# Addon-mapleCUx_Raspi-3V3-UART-CC2530-V00.net
KiCad netlist of a schematic drawn in EAGLE
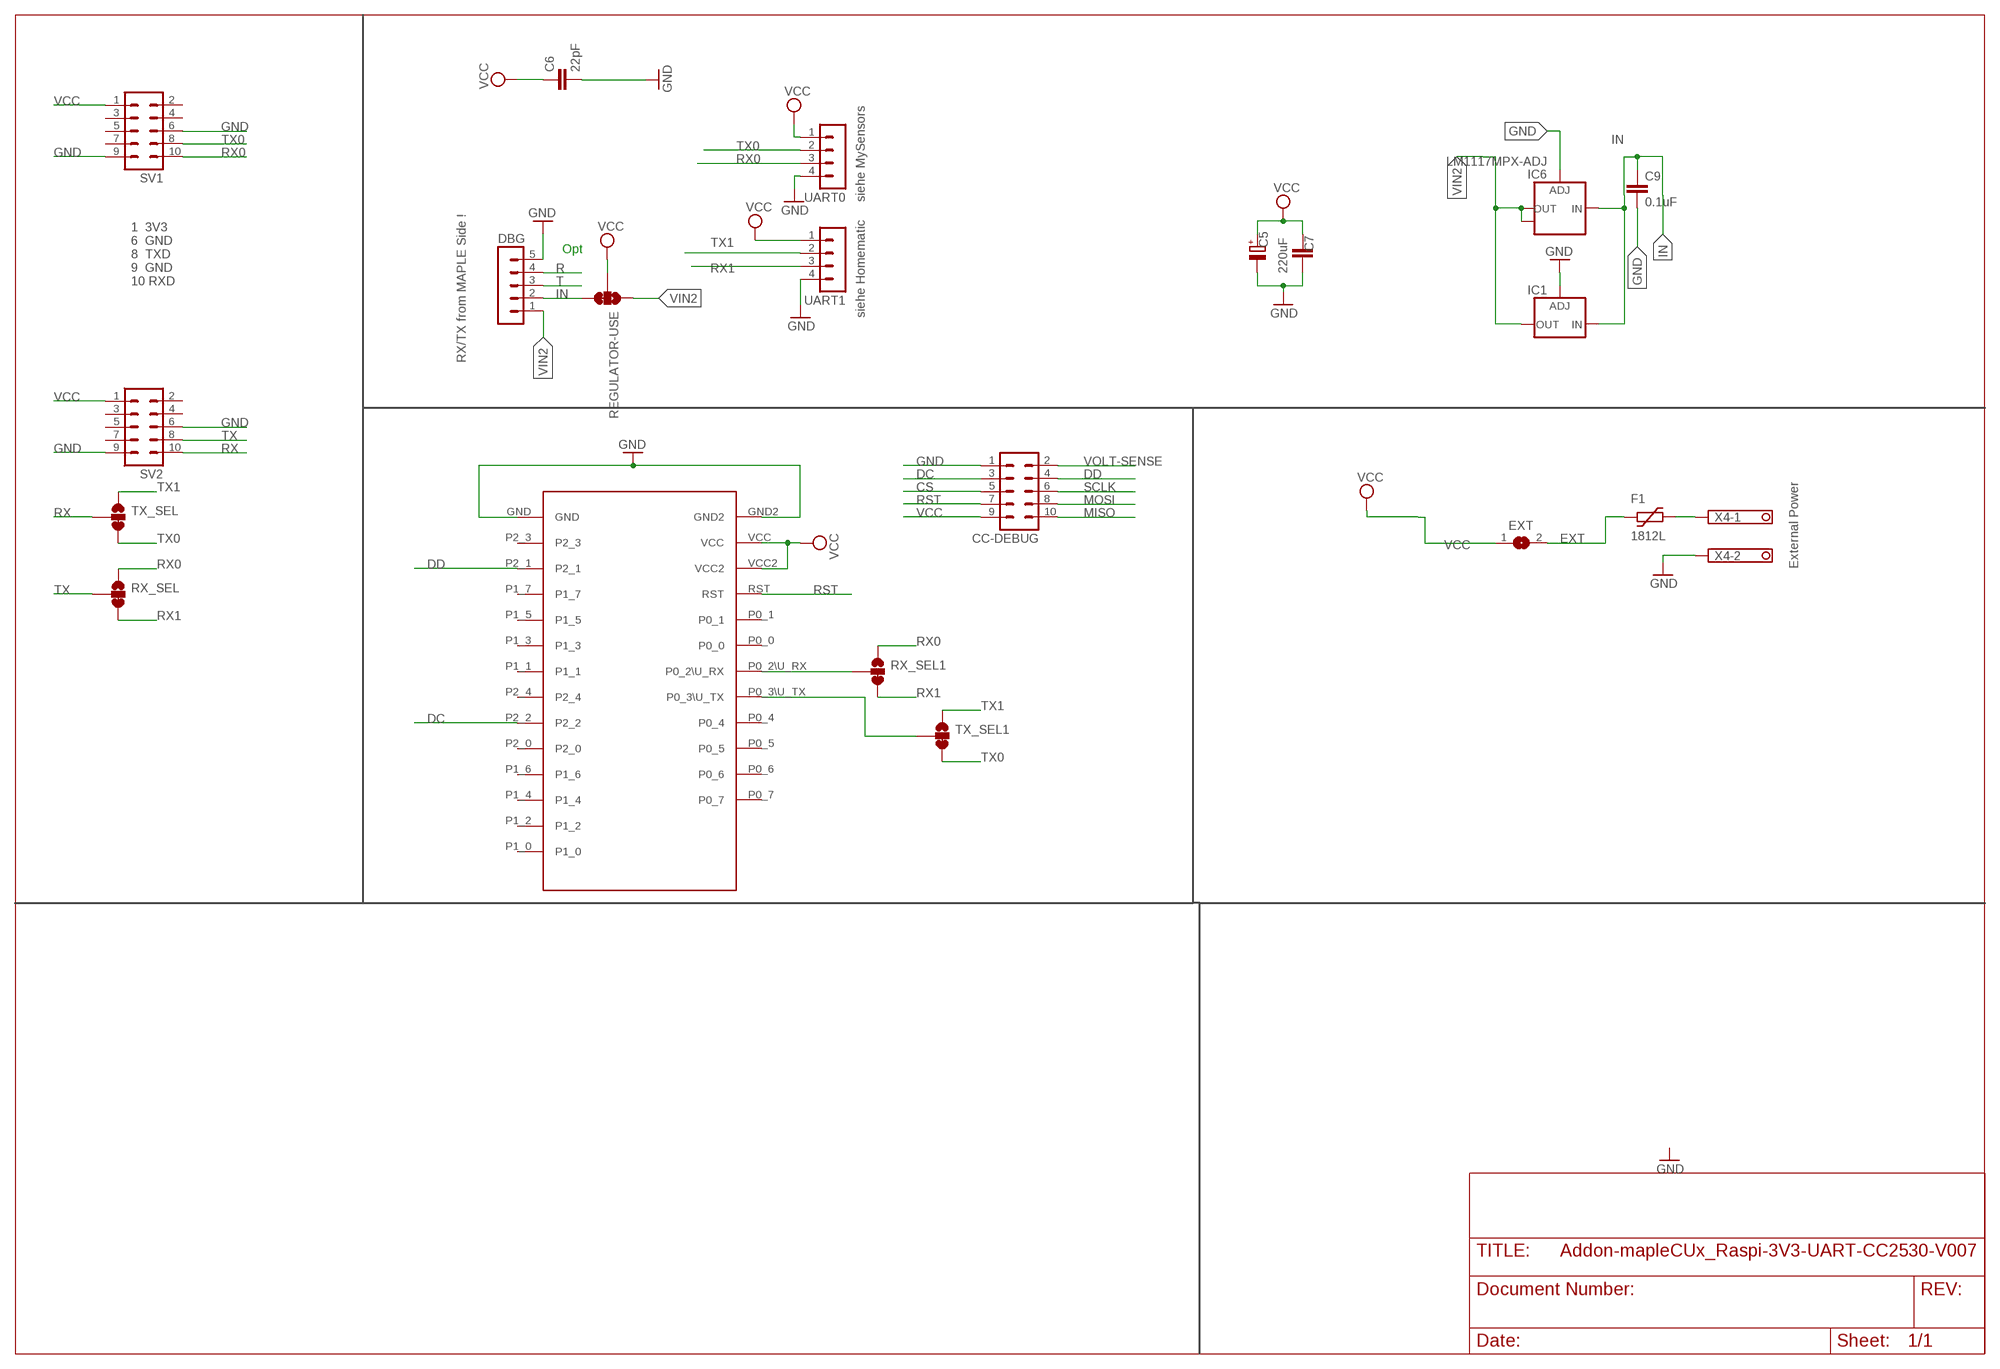
[diagram p0: schematic, sheet 1]

(export (version "E")
  (design (tool "Eeschema 10.0.6"))
  (components
    (comp (ref "C5")
      (value "220uF")
      (footprint "eagle-import:E5-8,5")
      (libsource (lib "eagle-import") (part "CPOL-EUE5-8.5"))
    )
    (comp (ref "C6")
      (value "22pF")
      (footprint "eagle-import:C0805")
      (libsource (lib "eagle-import") (part "C-EUC0805"))
    )
    (comp (ref "C7")
      (value "C-EUC1812")
      (footprint "eagle-import:C1812")
      (libsource (lib "eagle-import") (part "C-EUC1812"))
    )
    (comp (ref "C9")
      (value "0.1uF")
      (footprint "eagle-import:C1206")
      (libsource (lib "eagle-import") (part "C-EUC1206"))
    )
    (comp (ref "CC-DEBUG")
      (value "MA05-2")
      (footprint "eagle-import:MA05-2")
      (libsource (lib "eagle-import") (part "MA05-2"))
    )
    (comp (ref "DBG")
      (value "MA05-1")
      (footprint "eagle-import:MA05-1")
      (libsource (lib "eagle-import") (part "MA05-1"))
    )
    (comp (ref "EXT") (value "SJ") (footprint "eagle-import:SJ") (libsource (lib "eagle-import") (part "SJ")))
    (comp (ref "F1")
      (value "1812L")
      (footprint "eagle-import:1812L")
      (libsource (lib "eagle-import") (part "1812L"))
    )
    (comp (ref "IC1")
      (value "LD117ADT50TR")
      (footprint "eagle-import:DPACK")
      (libsource (lib "eagle-import") (part "LD117A?DT50TR"))
    )
    (comp (ref "IC6")
      (value "LM1117MPX-ADJ")
      (footprint "eagle-import:SOT223")
      (libsource (lib "eagle-import") (part "LM1117MPX-ADJ"))
    )
    (comp (ref "REGULATOR-USE")
      (value "JUMPER-SMT_3_1-NC_TRACE_SILK")
      (footprint "eagle-import:SMT-JUMPER_3_1-NC_TRACE_SILK")
      (libsource (lib "eagle-import") (part "JUMPER-SMT_3_1-NC_TRACE_SILK"))
    )
    (comp (ref "RX_SEL")
      (value "JUMPER-SMT_3_1-NC_TRACE_SILK")
      (footprint "eagle-import:SMT-JUMPER_3_1-NC_TRACE_SILK")
      (libsource (lib "eagle-import") (part "JUMPER-SMT_3_1-NC_TRACE_SILK"))
    )
    (comp (ref "RX_SEL1")
      (value "JUMPER-SMT_3_1-NC_TRACE_SILK")
      (footprint "eagle-import:SMT-JUMPER_3_1-NC_TRACE_SILK")
      (libsource (lib "eagle-import") (part "JUMPER-SMT_3_1-NC_TRACE_SILK"))
    )
    (comp (ref "SV1")
      (value "MA05-2")
      (footprint "eagle-import:MA05-2")
      (libsource (lib "eagle-import") (part "MA05-2"))
    )
    (comp (ref "SV2")
      (value "MA05-2")
      (footprint "eagle-import:MA05-2")
      (libsource (lib "eagle-import") (part "MA05-2"))
    )
    (comp (ref "TX_SEL")
      (value "JUMPER-SMT_3_1-NC_TRACE_SILK")
      (footprint "eagle-import:SMT-JUMPER_3_1-NC_TRACE_SILK")
      (libsource (lib "eagle-import") (part "JUMPER-SMT_3_1-NC_TRACE_SILK"))
    )
    (comp (ref "TX_SEL1")
      (value "JUMPER-SMT_3_1-NC_TRACE_SILK")
      (footprint "eagle-import:SMT-JUMPER_3_1-NC_TRACE_SILK")
      (libsource (lib "eagle-import") (part "JUMPER-SMT_3_1-NC_TRACE_SILK"))
    )
    (comp (ref "U$3")
      (value "CC2530_MODULE")
      (footprint "eagle-import:CC2530_DIL")
      (libsource (lib "eagle-import") (part "CC2530_MODULE"))
    )
    (comp (ref "UART0")
      (value "MA04-1")
      (footprint "eagle-import:MA04-1")
      (libsource (lib "eagle-import") (part "MA04-1"))
    )
    (comp (ref "UART1")
      (value "MA04-1")
      (footprint "eagle-import:MA04-1")
      (libsource (lib "eagle-import") (part "MA04-1"))
    )
    (comp (ref "X4")
      (value "1751248")
      (footprint "eagle-import:1751248")
      (libsource (lib "eagle-import") (part "1751248"))
    )
  )
  (nets
    (net (code "1") (name "/CS") (class "Default")
      (node (ref "CC-DEBUG") (pin "5") (pinfunction "5_5") (pintype "passive"))
    )
    (net (code "2") (name "/DC") (class "Default")
      (node (ref "CC-DEBUG") (pin "3") (pinfunction "3_3") (pintype "passive"))
      (node (ref "U$3") (pin "P2_2") (pinfunction "P2_2_P2_2") (pintype "bidirectional"))
    )
    (net (code "3") (name "/DD") (class "Default")
      (node (ref "CC-DEBUG") (pin "4") (pinfunction "4_4") (pintype "passive"))
      (node (ref "U$3") (pin "P2_1") (pinfunction "P2_1_P2_1") (pintype "bidirectional"))
    )
    (net (code "4") (name "/EXT") (class "Default")
      (node (ref "EXT") (pin "2") (pinfunction "2_2") (pintype "passive"))
      (node (ref "F1") (pin "P$1") (pinfunction "1_P$1") (pintype "passive"))
    )
    (net (code "5") (name "/MISO") (class "Default")
      (node (ref "CC-DEBUG") (pin "10") (pinfunction "10_10") (pintype "passive"))
    )
    (net (code "6") (name "/MOSI") (class "Default")
      (node (ref "CC-DEBUG") (pin "8") (pinfunction "8_8") (pintype "passive"))
    )
    (net (code "7") (name "/R") (class "Default")
      (node (ref "DBG") (pin "4") (pinfunction "4_4") (pintype "passive"))
    )
    (net (code "8") (name "/RST") (class "Default")
      (node (ref "CC-DEBUG") (pin "7") (pinfunction "7_7") (pintype "passive"))
      (node (ref "U$3") (pin "RST") (pinfunction "RST_RST") (pintype "bidirectional"))
    )
    (net (code "9") (name "/RX") (class "Default")
      (node (ref "SV2") (pin "10") (pinfunction "10_10") (pintype "passive"))
      (node (ref "TX_SEL") (pin "2") (pinfunction "2_2") (pintype "passive"))
    )
    (net (code "10") (name "/RX0") (class "Default")
      (node (ref "RX_SEL") (pin "1") (pinfunction "1_1") (pintype "passive"))
      (node (ref "RX_SEL1") (pin "1") (pinfunction "1_1") (pintype "passive"))
      (node (ref "SV1") (pin "10") (pinfunction "10_10") (pintype "passive"))
      (node (ref "UART0") (pin "3") (pinfunction "3_3") (pintype "passive"))
    )
    (net (code "11") (name "/RX1") (class "Default")
      (node (ref "RX_SEL") (pin "3") (pinfunction "3_3") (pintype "passive"))
      (node (ref "RX_SEL1") (pin "3") (pinfunction "3_3") (pintype "passive"))
      (node (ref "UART1") (pin "3") (pinfunction "3_3") (pintype "passive"))
    )
    (net (code "12") (name "/SCLK") (class "Default")
      (node (ref "CC-DEBUG") (pin "6") (pinfunction "6_6") (pintype "passive"))
    )
    (net (code "13") (name "/T") (class "Default")
      (node (ref "DBG") (pin "3") (pinfunction "3_3") (pintype "passive"))
    )
    (net (code "14") (name "/TX") (class "Default")
      (node (ref "RX_SEL") (pin "2") (pinfunction "2_2") (pintype "passive"))
      (node (ref "SV2") (pin "8") (pinfunction "8_8") (pintype "passive"))
    )
    (net (code "15") (name "/TX0") (class "Default")
      (node (ref "SV1") (pin "8") (pinfunction "8_8") (pintype "passive"))
      (node (ref "TX_SEL") (pin "3") (pinfunction "3_3") (pintype "passive"))
      (node (ref "TX_SEL1") (pin "3") (pinfunction "3_3") (pintype "passive"))
      (node (ref "UART0") (pin "2") (pinfunction "2_2") (pintype "passive"))
    )
    (net (code "16") (name "/TX1") (class "Default")
      (node (ref "TX_SEL") (pin "1") (pinfunction "1_1") (pintype "passive"))
      (node (ref "TX_SEL1") (pin "1") (pinfunction "1_1") (pintype "passive"))
      (node (ref "UART1") (pin "2") (pinfunction "2_2") (pintype "passive"))
    )
    (net (code "17") (name "/VOLT-SENSE") (class "Default")
      (node (ref "CC-DEBUG") (pin "2") (pinfunction "2_2") (pintype "passive"))
    )
    (net (code "18") (name "GND") (class "Default")
      (node (ref "C5") (pin "-") (pinfunction "-_-") (pintype "passive"))
      (node (ref "C6") (pin "2") (pinfunction "2_2") (pintype "passive"))
      (node (ref "C7") (pin "1") (pinfunction "1_1") (pintype "passive"))
      (node (ref "C9") (pin "2") (pinfunction "2_2") (pintype "passive"))
      (node (ref "CC-DEBUG") (pin "1") (pinfunction "1_1") (pintype "passive"))
      (node (ref "DBG") (pin "5") (pinfunction "5_5") (pintype "passive"))
      (node (ref "IC1") (pin "1") (pinfunction "ADJ_1") (pintype "input"))
      (node (ref "IC6") (pin "1") (pinfunction "ADJ_1") (pintype "input"))
      (node (ref "SV1") (pin "6") (pinfunction "6_6") (pintype "passive"))
      (node (ref "SV1") (pin "9") (pinfunction "9_9") (pintype "passive"))
      (node (ref "SV2") (pin "6") (pinfunction "6_6") (pintype "passive"))
      (node (ref "SV2") (pin "9") (pinfunction "9_9") (pintype "passive"))
      (node (ref "U$3") (pin "GND") (pinfunction "GND_GND") (pintype "bidirectional"))
      (node (ref "U$3") (pin "GND2") (pinfunction "GND2_GND2") (pintype "bidirectional"))
      (node (ref "UART0") (pin "4") (pinfunction "4_4") (pintype "passive"))
      (node (ref "UART1") (pin "4") (pinfunction "4_4") (pintype "passive"))
      (node (ref "X4") (pin "2") (pinfunction "K_2") (pintype "passive"))
    )
    (net (code "19") (name "IN") (class "Default")
      (node (ref "C9") (pin "1") (pinfunction "1_1") (pintype "passive"))
      (node (ref "DBG") (pin "2") (pinfunction "2_2") (pintype "passive"))
      (node (ref "IC1") (pin "3") (pinfunction "IN_3") (pintype "input"))
      (node (ref "IC6") (pin "3") (pinfunction "IN_3") (pintype "input"))
      (node (ref "REGULATOR-USE") (pin "3") (pinfunction "3_3") (pintype "passive"))
    )
    (net (code "20") (name "Net-(F1-2)") (class "Default")
      (node (ref "F1") (pin "P$2") (pinfunction "2_P$2") (pintype "passive"))
      (node (ref "X4") (pin "1") (pinfunction "K_1") (pintype "passive"))
    )
    (net (code "21") (name "Net-(RX_SEL1-Pad2)") (class "Default")
      (node (ref "RX_SEL1") (pin "2") (pinfunction "2_2") (pintype "passive"))
      (node (ref "U$3") (pin "P0_2\\U_RX") (pinfunction "P0_2\\U_RX_P0_2\\U_RX") (pintype "bidirectional"))
    )
    (net (code "22") (name "Net-(TX_SEL1-Pad2)") (class "Default")
      (node (ref "TX_SEL1") (pin "2") (pinfunction "2_2") (pintype "passive"))
      (node (ref "U$3") (pin "P0_3\\U_TX") (pinfunction "P0_3\\U_TX_P0_3\\U_TX") (pintype "bidirectional"))
    )
    (net (code "23") (name "VCC") (class "Default")
      (node (ref "C5") (pin "+") (pinfunction "+_+") (pintype "passive"))
      (node (ref "C6") (pin "1") (pinfunction "1_1") (pintype "passive"))
      (node (ref "C7") (pin "2") (pinfunction "2_2") (pintype "passive"))
      (node (ref "CC-DEBUG") (pin "9") (pinfunction "9_9") (pintype "passive"))
      (node (ref "EXT") (pin "1") (pinfunction "1_1") (pintype "passive"))
      (node (ref "REGULATOR-USE") (pin "2") (pinfunction "2_2") (pintype "passive"))
      (node (ref "SV1") (pin "1") (pinfunction "1_1") (pintype "passive"))
      (node (ref "SV2") (pin "1") (pinfunction "1_1") (pintype "passive"))
      (node (ref "U$3") (pin "VCC") (pinfunction "VCC_VCC") (pintype "bidirectional"))
      (node (ref "U$3") (pin "VCC2") (pinfunction "VCC2_VCC2") (pintype "bidirectional"))
      (node (ref "UART0") (pin "1") (pinfunction "1_1") (pintype "passive"))
      (node (ref "UART1") (pin "1") (pinfunction "1_1") (pintype "passive"))
    )
    (net (code "24") (name "VIN2") (class "Default")
      (node (ref "DBG") (pin "1") (pinfunction "1_1") (pintype "passive"))
      (node (ref "IC1") (pin "4") (pinfunction "OUT_4") (pintype "passive"))
      (node (ref "IC6") (pin "2") (pinfunction "OUT_2") (pintype "passive"))
      (node (ref "IC6") (pin "TAB") (pinfunction "OUT1_TAB") (pintype "passive"))
      (node (ref "REGULATOR-USE") (pin "1") (pinfunction "1_1") (pintype "passive"))
    )
    (net (code "25") (name "unconnected-(SV1-Pad2)") (class "Default")
      (node (ref "SV1") (pin "2") (pinfunction "2_2") (pintype "passive"))
    )
    (net (code "26") (name "unconnected-(SV1-Pad3)") (class "Default")
      (node (ref "SV1") (pin "3") (pinfunction "3_3") (pintype "passive"))
    )
    (net (code "27") (name "unconnected-(SV1-Pad4)") (class "Default")
      (node (ref "SV1") (pin "4") (pinfunction "4_4") (pintype "passive"))
    )
    (net (code "28") (name "unconnected-(SV1-Pad5)") (class "Default")
      (node (ref "SV1") (pin "5") (pinfunction "5_5") (pintype "passive"))
    )
    (net (code "29") (name "unconnected-(SV1-Pad7)") (class "Default")
      (node (ref "SV1") (pin "7") (pinfunction "7_7") (pintype "passive"))
    )
    (net (code "30") (name "unconnected-(SV2-Pad2)") (class "Default")
      (node (ref "SV2") (pin "2") (pinfunction "2_2") (pintype "passive"))
    )
    (net (code "31") (name "unconnected-(SV2-Pad3)") (class "Default")
      (node (ref "SV2") (pin "3") (pinfunction "3_3") (pintype "passive"))
    )
    (net (code "32") (name "unconnected-(SV2-Pad4)") (class "Default")
      (node (ref "SV2") (pin "4") (pinfunction "4_4") (pintype "passive"))
    )
    (net (code "33") (name "unconnected-(SV2-Pad5)") (class "Default")
      (node (ref "SV2") (pin "5") (pinfunction "5_5") (pintype "passive"))
    )
    (net (code "34") (name "unconnected-(SV2-Pad7)") (class "Default")
      (node (ref "SV2") (pin "7") (pinfunction "7_7") (pintype "passive"))
    )
    (net (code "35") (name "unconnected-(U$3-PadP0_0)") (class "Default")
      (node (ref "U$3") (pin "P0_0") (pinfunction "P0_0_P0_0") (pintype "bidirectional"))
    )
    (net (code "36") (name "unconnected-(U$3-PadP0_1)") (class "Default")
      (node (ref "U$3") (pin "P0_1") (pinfunction "P0_1_P0_1") (pintype "bidirectional"))
    )
    (net (code "37") (name "unconnected-(U$3-PadP0_4)") (class "Default")
      (node (ref "U$3") (pin "P0_4") (pinfunction "P0_4_P0_4") (pintype "bidirectional"))
    )
    (net (code "38") (name "unconnected-(U$3-PadP0_5)") (class "Default")
      (node (ref "U$3") (pin "P0_5") (pinfunction "P0_5_P0_5") (pintype "bidirectional"))
    )
    (net (code "39") (name "unconnected-(U$3-PadP0_6)") (class "Default")
      (node (ref "U$3") (pin "P0_6") (pinfunction "P0_6_P0_6") (pintype "bidirectional"))
    )
    (net (code "40") (name "unconnected-(U$3-PadP0_7)") (class "Default")
      (node (ref "U$3") (pin "P0_7") (pinfunction "P0_7_P0_7") (pintype "bidirectional"))
    )
    (net (code "41") (name "unconnected-(U$3-PadP1_0)") (class "Default")
      (node (ref "U$3") (pin "P1_0") (pinfunction "P1_0_P1_0") (pintype "bidirectional"))
    )
    (net (code "42") (name "unconnected-(U$3-PadP1_1)") (class "Default")
      (node (ref "U$3") (pin "P1_1") (pinfunction "P1_1_P1_1") (pintype "bidirectional"))
    )
    (net (code "43") (name "unconnected-(U$3-PadP1_2)") (class "Default")
      (node (ref "U$3") (pin "P1_2") (pinfunction "P1_2_P1_2") (pintype "bidirectional"))
    )
    (net (code "44") (name "unconnected-(U$3-PadP1_3)") (class "Default")
      (node (ref "U$3") (pin "P1_3") (pinfunction "P1_3_P1_3") (pintype "bidirectional"))
    )
    (net (code "45") (name "unconnected-(U$3-PadP1_4)") (class "Default")
      (node (ref "U$3") (pin "P1_4") (pinfunction "P1_4_P1_4") (pintype "bidirectional"))
    )
    (net (code "46") (name "unconnected-(U$3-PadP1_5)") (class "Default")
      (node (ref "U$3") (pin "P1_5") (pinfunction "P1_5_P1_5") (pintype "bidirectional"))
    )
    (net (code "47") (name "unconnected-(U$3-PadP1_6)") (class "Default")
      (node (ref "U$3") (pin "P1_6") (pinfunction "P1_6_P1_6") (pintype "bidirectional"))
    )
    (net (code "48") (name "unconnected-(U$3-PadP1_7)") (class "Default")
      (node (ref "U$3") (pin "P1_7") (pinfunction "P1_7_P1_7") (pintype "bidirectional"))
    )
    (net (code "49") (name "unconnected-(U$3-PadP2_0)") (class "Default")
      (node (ref "U$3") (pin "P2_0") (pinfunction "P2_0_P2_0") (pintype "bidirectional"))
    )
    (net (code "50") (name "unconnected-(U$3-PadP2_3)") (class "Default")
      (node (ref "U$3") (pin "P2_3") (pinfunction "P2_3_P2_3") (pintype "bidirectional"))
    )
    (net (code "51") (name "unconnected-(U$3-PadP2_4)") (class "Default")
      (node (ref "U$3") (pin "P2_4") (pinfunction "P2_4_P2_4") (pintype "bidirectional"))
    )
  )
)
